# sound-barnacle.net
KiCad netlist of a schematic drawn in EAGLE
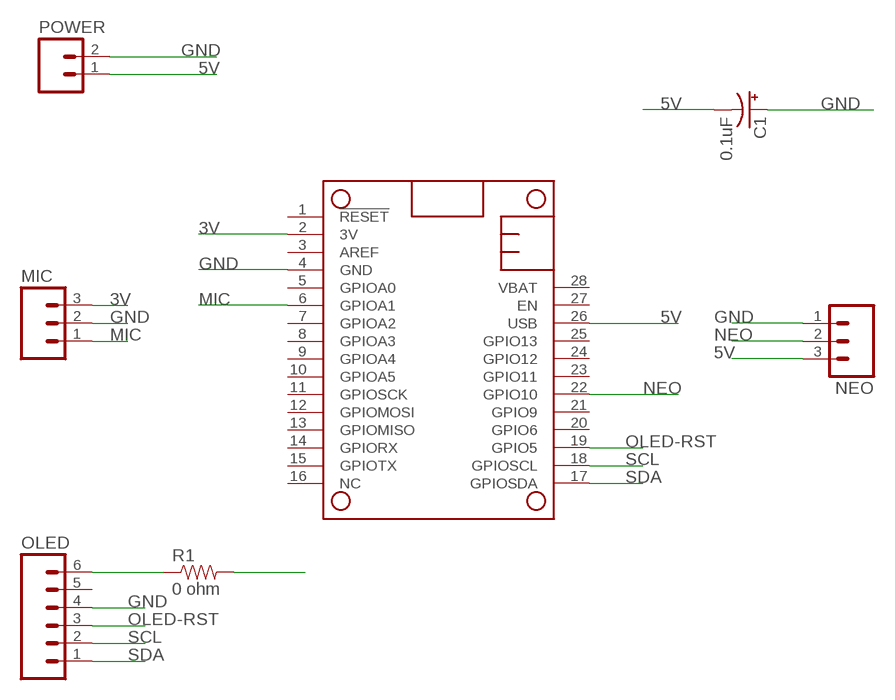
[diagram p0: schematic, sheet 1]

(export (version "E")
  (design (tool "Eeschema 10.0.6"))
  (components
    (comp (ref "C1")
      (value "0.1uF")
      (footprint "eagle-import:B45181B")
      (libsource (lib "eagle-import") (part "CPOL-USB45181B"))
    )
    (comp (ref "MIC")
      (value "M03LOCK_LONGPADS")
      (footprint "eagle-import:1X03_LOCK_LONGPADS")
      (libsource (lib "eagle-import") (part "M03LOCK_LONGPADS"))
    )
    (comp (ref "MS1")
      (value "FEATHERWING")
      (footprint "eagle-import:FEATHERWING")
      (libsource (lib "eagle-import") (part "FEATHERWING"))
    )
    (comp (ref "NEO")
      (value "M03LOCK_LONGPADS")
      (footprint "eagle-import:1X03_LOCK_LONGPADS")
      (libsource (lib "eagle-import") (part "M03LOCK_LONGPADS"))
    )
    (comp (ref "OLED")
      (value "M06LOCK_LONGPADS")
      (footprint "eagle-import:1X06_LOCK_LONGPADS")
      (libsource (lib "eagle-import") (part "M06LOCK_LONGPADS"))
    )
    (comp (ref "POWER")
      (value "M02LOCK_LONGPADS")
      (footprint "eagle-import:1X02_LOCK_LONGPADS")
      (libsource (lib "eagle-import") (part "M02LOCK_LONGPADS"))
    )
    (comp (ref "R1")
      (value "0 ohm")
      (footprint "eagle-import:AXIAL-0.3")
      (libsource (lib "eagle-import") (part "RESISTORAXIAL-0.3"))
    )
  )
  (nets
    (net (code "1") (name "/3V") (class "Default")
      (node (ref "MIC") (pin "3") (pinfunction "3_3") (pintype "passive"))
      (node (ref "MS1") (pin "2") (pinfunction "3V_2") (pintype "power_in"))
      (node (ref "R1") (pin "P$2") (pinfunction "2_P$2") (pintype "passive"))
    )
    (net (code "2") (name "/5V") (class "Default")
      (node (ref "C1") (pin "-") (pinfunction "-_-") (pintype "passive"))
      (node (ref "MS1") (pin "26") (pinfunction "USB_26") (pintype "power_in"))
      (node (ref "NEO") (pin "3") (pinfunction "3_3") (pintype "passive"))
      (node (ref "POWER") (pin "1") (pinfunction "1_1") (pintype "passive"))
    )
    (net (code "3") (name "/GND") (class "Default")
      (node (ref "C1") (pin "+") (pinfunction "+_+") (pintype "passive"))
      (node (ref "MIC") (pin "2") (pinfunction "2_2") (pintype "passive"))
      (node (ref "MS1") (pin "4") (pinfunction "GND_4") (pintype "power_in"))
      (node (ref "NEO") (pin "1") (pinfunction "1_1") (pintype "passive"))
      (node (ref "OLED") (pin "4") (pinfunction "4_4") (pintype "passive"))
      (node (ref "POWER") (pin "2") (pinfunction "2_2") (pintype "passive"))
    )
    (net (code "4") (name "/MIC") (class "Default")
      (node (ref "MIC") (pin "1") (pinfunction "1_1") (pintype "passive"))
      (node (ref "MS1") (pin "6") (pinfunction "GPIOA1_6") (pintype "bidirectional"))
    )
    (net (code "5") (name "/NEO") (class "Default")
      (node (ref "MS1") (pin "22") (pinfunction "GPIO10_22") (pintype "bidirectional"))
      (node (ref "NEO") (pin "2") (pinfunction "2_2") (pintype "passive"))
    )
    (net (code "6") (name "/OLED-RST") (class "Default")
      (node (ref "MS1") (pin "19") (pinfunction "GPIO5_19") (pintype "bidirectional"))
      (node (ref "OLED") (pin "3") (pinfunction "3_3") (pintype "passive"))
    )
    (net (code "7") (name "/SCL") (class "Default")
      (node (ref "MS1") (pin "18") (pinfunction "GPIOSCL_18") (pintype "bidirectional"))
      (node (ref "OLED") (pin "2") (pinfunction "2_2") (pintype "passive"))
    )
    (net (code "8") (name "/SDA") (class "Default")
      (node (ref "MS1") (pin "17") (pinfunction "GPIOSDA_17") (pintype "bidirectional"))
      (node (ref "OLED") (pin "1") (pinfunction "1_1") (pintype "passive"))
    )
    (net (code "9") (name "/VBAT") (class "Default")
      (node (ref "MS1") (pin "28") (pinfunction "VBAT_28") (pintype "power_in"))
    )
    (net (code "10") (name "Net-(R1-1)") (class "Default")
      (node (ref "OLED") (pin "6") (pinfunction "6_6") (pintype "passive"))
      (node (ref "R1") (pin "P$1") (pinfunction "1_P$1") (pintype "passive"))
    )
    (net (code "11") (name "unconnected-(MS1-AREF-Pad3)") (class "Default")
      (node (ref "MS1") (pin "3") (pinfunction "AREF_3") (pintype "passive"))
    )
    (net (code "12") (name "unconnected-(MS1-EN-Pad27)") (class "Default")
      (node (ref "MS1") (pin "27") (pinfunction "EN_27") (pintype "passive"))
    )
    (net (code "13") (name "unconnected-(MS1-GPIO6-Pad20)") (class "Default")
      (node (ref "MS1") (pin "20") (pinfunction "GPIO6_20") (pintype "bidirectional"))
    )
    (net (code "14") (name "unconnected-(MS1-GPIO9-Pad21)") (class "Default")
      (node (ref "MS1") (pin "21") (pinfunction "GPIO9_21") (pintype "bidirectional"))
    )
    (net (code "15") (name "unconnected-(MS1-GPIO11-Pad23)") (class "Default")
      (node (ref "MS1") (pin "23") (pinfunction "GPIO11_23") (pintype "bidirectional"))
    )
    (net (code "16") (name "unconnected-(MS1-GPIO12-Pad24)") (class "Default")
      (node (ref "MS1") (pin "24") (pinfunction "GPIO12_24") (pintype "bidirectional"))
    )
    (net (code "17") (name "unconnected-(MS1-GPIO13-Pad25)") (class "Default")
      (node (ref "MS1") (pin "25") (pinfunction "GPIO13_25") (pintype "bidirectional"))
    )
    (net (code "18") (name "unconnected-(MS1-GPIOA0-Pad5)") (class "Default")
      (node (ref "MS1") (pin "5") (pinfunction "GPIOA0_5") (pintype "bidirectional"))
    )
    (net (code "19") (name "unconnected-(MS1-GPIOA2-Pad7)") (class "Default")
      (node (ref "MS1") (pin "7") (pinfunction "GPIOA2_7") (pintype "bidirectional"))
    )
    (net (code "20") (name "unconnected-(MS1-GPIOA3-Pad8)") (class "Default")
      (node (ref "MS1") (pin "8") (pinfunction "GPIOA3_8") (pintype "bidirectional"))
    )
    (net (code "21") (name "unconnected-(MS1-GPIOA4-Pad9)") (class "Default")
      (node (ref "MS1") (pin "9") (pinfunction "GPIOA4_9") (pintype "bidirectional"))
    )
    (net (code "22") (name "unconnected-(MS1-GPIOA5-Pad10)") (class "Default")
      (node (ref "MS1") (pin "10") (pinfunction "GPIOA5_10") (pintype "bidirectional"))
    )
    (net (code "23") (name "unconnected-(MS1-GPIOMISO-Pad13)") (class "Default")
      (node (ref "MS1") (pin "13") (pinfunction "GPIOMISO_13") (pintype "bidirectional"))
    )
    (net (code "24") (name "unconnected-(MS1-GPIOMOSI-Pad12)") (class "Default")
      (node (ref "MS1") (pin "12") (pinfunction "GPIOMOSI_12") (pintype "bidirectional"))
    )
    (net (code "25") (name "unconnected-(MS1-GPIORX-Pad14)") (class "Default")
      (node (ref "MS1") (pin "14") (pinfunction "GPIORX_14") (pintype "bidirectional"))
    )
    (net (code "26") (name "unconnected-(MS1-GPIOSCK-Pad11)") (class "Default")
      (node (ref "MS1") (pin "11") (pinfunction "GPIOSCK_11") (pintype "bidirectional"))
    )
    (net (code "27") (name "unconnected-(MS1-GPIOTX-Pad15)") (class "Default")
      (node (ref "MS1") (pin "15") (pinfunction "GPIOTX_15") (pintype "bidirectional"))
    )
    (net (code "28") (name "unconnected-(MS1-NC-Pad16)") (class "Default")
      (node (ref "MS1") (pin "16") (pinfunction "NC_16") (pintype "passive"))
    )
    (net (code "29") (name "unconnected-(MS1-~{RESET}-Pad1)") (class "Default")
      (node (ref "MS1") (pin "1") (pinfunction "~{RESET}_1") (pintype "input"))
    )
    (net (code "30") (name "unconnected-(OLED-Pad5)") (class "Default")
      (node (ref "OLED") (pin "5") (pinfunction "5_5") (pintype "passive"))
    )
  )
)
